# cdf-single-driver.net
KiCad netlist of a schematic drawn in EAGLE
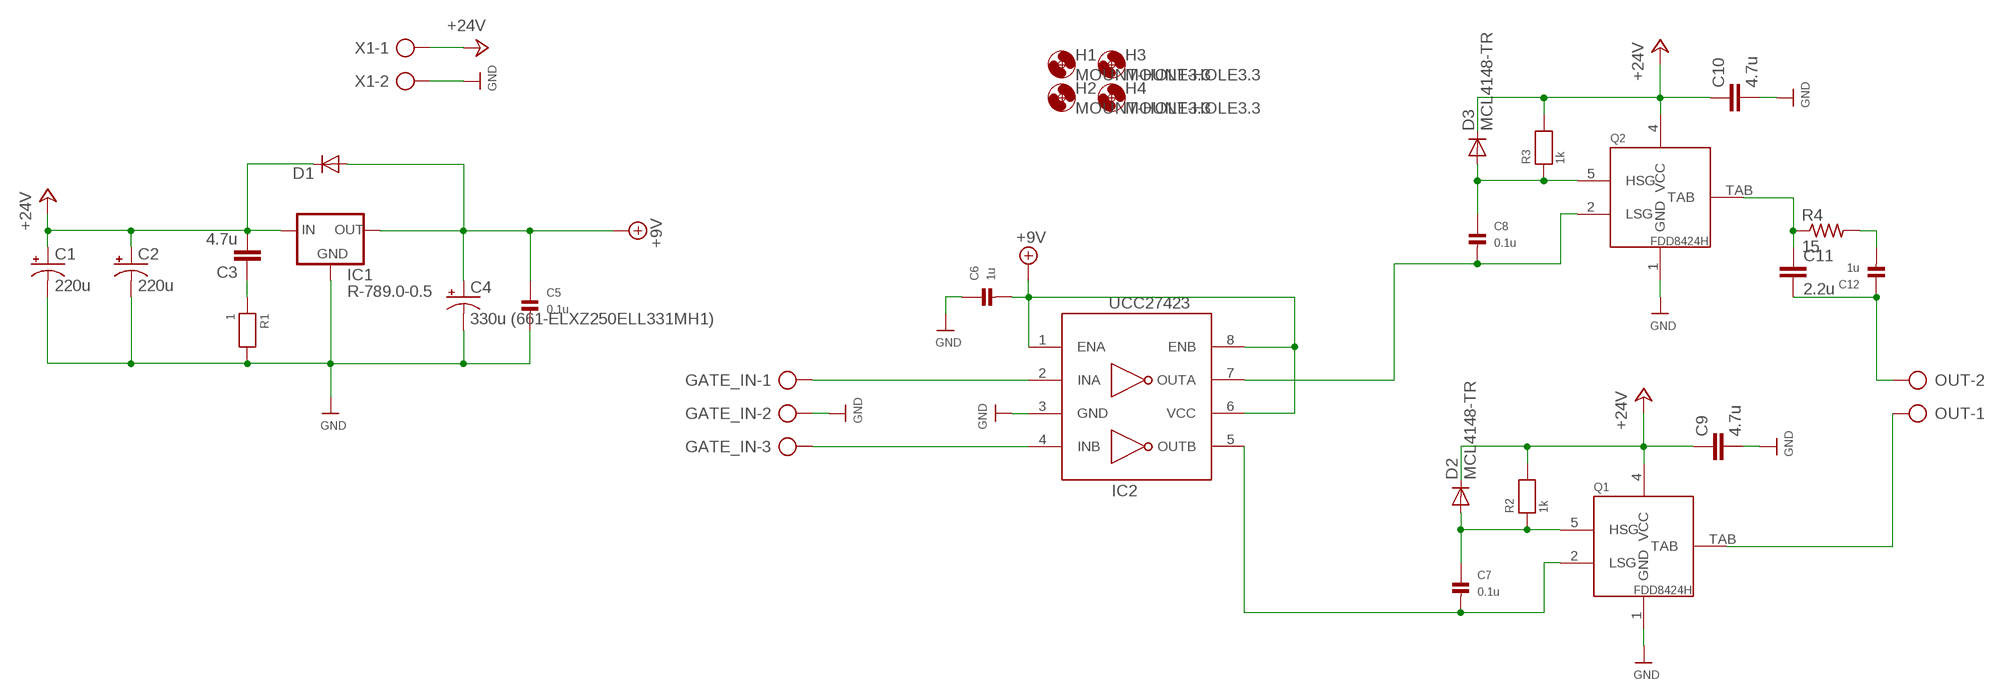
[diagram p0: schematic, sheet 1]

(export (version "E")
  (design (tool "Eeschema 10.0.6"))
  (components
    (comp (ref "C1")
      (value "220u")
      (footprint "eagle-import:E3,5-8")
      (libsource (lib "eagle-import") (part "CPOL-USE3.5-8"))
    )
    (comp (ref "C2")
      (value "220u")
      (footprint "eagle-import:E3,5-8")
      (libsource (lib "eagle-import") (part "CPOL-USE3.5-8"))
    )
    (comp (ref "C3")
      (value "4.7u")
      (footprint "eagle-import:C1210")
      (libsource (lib "eagle-import") (part "C-EUC1210"))
    )
    (comp (ref "C4")
      (value "330u (661-ELXZ250ELL331MH1)")
      (footprint "eagle-import:E3,5-8")
      (libsource (lib "eagle-import") (part "CPOL-USE3.5-8"))
    )
    (comp (ref "C5")
      (value "0.1u")
      (footprint "eagle-import:0805")
      (libsource (lib "eagle-import") (part "CAP_CERAMIC0805"))
    )
    (comp (ref "C6")
      (value "1u")
      (footprint "eagle-import:1206")
      (libsource (lib "eagle-import") (part "CAP_CERAMIC1206"))
    )
    (comp (ref "C7")
      (value "0.1u")
      (footprint "eagle-import:0805")
      (libsource (lib "eagle-import") (part "CAP_CERAMIC0805"))
    )
    (comp (ref "C8")
      (value "0.1u")
      (footprint "eagle-import:0805")
      (libsource (lib "eagle-import") (part "CAP_CERAMIC0805"))
    )
    (comp (ref "C9")
      (value "4.7u")
      (footprint "eagle-import:C1210")
      (libsource (lib "eagle-import") (part "C-EUC1210"))
    )
    (comp (ref "C10")
      (value "4.7u")
      (footprint "eagle-import:C1210")
      (libsource (lib "eagle-import") (part "C-EUC1210"))
    )
    (comp (ref "C11")
      (value "2.2u")
      (footprint "eagle-import:C1210")
      (libsource (lib "eagle-import") (part "C-EUC1210"))
    )
    (comp (ref "C12")
      (value "1u")
      (footprint "eagle-import:1206")
      (libsource (lib "eagle-import") (part "CAP_CERAMIC1206"))
    )
    (comp (ref "D1")
      (value "DIODE-SOD123")
      (footprint "eagle-import:SOD123")
      (libsource (lib "eagle-import") (part "DIODE-SOD123"))
    )
    (comp (ref "D2")
      (value "MCL4148-TR")
      (footprint "eagle-import:MICROMELF-W")
      (libsource (lib "eagle-import") (part "DIODE-MICROMELF-W"))
    )
    (comp (ref "D3")
      (value "MCL4148-TR")
      (footprint "eagle-import:MICROMELF-W")
      (libsource (lib "eagle-import") (part "DIODE-MICROMELF-W"))
    )
    (comp (ref "GATE_IN")
      (value "AK500/3")
      (footprint "eagle-import:AK500_3")
      (libsource (lib "eagle-import") (part "AK500/3"))
    )
    (comp (ref "H1")
      (value "MOUNT-HOLE3.3")
      (footprint "eagle-import:3,3")
      (libsource (lib "eagle-import") (part "MOUNT-HOLE3.3"))
    )
    (comp (ref "H2")
      (value "MOUNT-HOLE3.3")
      (footprint "eagle-import:3,3")
      (libsource (lib "eagle-import") (part "MOUNT-HOLE3.3"))
    )
    (comp (ref "H3")
      (value "MOUNT-HOLE3.3")
      (footprint "eagle-import:3,3")
      (libsource (lib "eagle-import") (part "MOUNT-HOLE3.3"))
    )
    (comp (ref "H4")
      (value "MOUNT-HOLE3.3")
      (footprint "eagle-import:3,3")
      (libsource (lib "eagle-import") (part "MOUNT-HOLE3.3"))
    )
    (comp (ref "IC1")
      (value "R-789.0-0.5")
      (footprint "eagle-import:SIP3")
      (fields (field (name "MF") "Recom") (field (name "MPN") "R-789.0-05"))
      (libsource (lib "eagle-import") (part "R-78-0.59.0"))
    )
    (comp (ref "IC2")
      (value "UCC27423")
      (footprint "eagle-import:SOIC8")
      (libsource (lib "eagle-import") (part "UCC27423"))
    )
    (comp (ref "OUT")
      (value "AK500/2")
      (footprint "eagle-import:AK500_2")
      (libsource (lib "eagle-import") (part "AK500/2"))
    )
    (comp (ref "Q1")
      (value "FDD8424H")
      (footprint "eagle-import:TO252-4")
      (libsource (lib "eagle-import") (part "FDD8424H"))
    )
    (comp (ref "Q2")
      (value "FDD8424H")
      (footprint "eagle-import:TO252-4")
      (libsource (lib "eagle-import") (part "FDD8424H"))
    )
    (comp (ref "R1")
      (value "1")
      (footprint "eagle-import:0805")
      (libsource (lib "eagle-import") (part "RESISTOR0805"))
    )
    (comp (ref "R2")
      (value "1k")
      (footprint "eagle-import:0805")
      (libsource (lib "eagle-import") (part "RESISTOR0805"))
    )
    (comp (ref "R3")
      (value "1k")
      (footprint "eagle-import:0805")
      (libsource (lib "eagle-import") (part "RESISTOR0805"))
    )
    (comp (ref "R4")
      (value "15")
      (footprint "eagle-import:R1210")
      (libsource (lib "eagle-import") (part "R-US_R1210"))
    )
    (comp (ref "X1")
      (value "AK500/2")
      (footprint "eagle-import:AK500_2")
      (libsource (lib "eagle-import") (part "AK500/2"))
    )
  )
  (nets
    (net (code "1") (name "+9V") (class "Default")
      (node (ref "C4") (pin "+") (pinfunction "+_+") (pintype "passive"))
      (node (ref "C5") (pin "1") (pinfunction "P$1_1") (pintype "passive"))
      (node (ref "C6") (pin "2") (pinfunction "P$2_2") (pintype "passive"))
      (node (ref "D1") (pin "A") (pinfunction "A_A") (pintype "passive"))
      (node (ref "IC1") (pin "3") (pinfunction "OUT_3") (pintype "passive"))
      (node (ref "IC2") (pin "1") (pinfunction "ENA_1") (pintype "bidirectional"))
      (node (ref "IC2") (pin "6") (pinfunction "VCC_6") (pintype "bidirectional"))
      (node (ref "IC2") (pin "8") (pinfunction "ENB_8") (pintype "bidirectional"))
    )
    (net (code "2") (name "+24V") (class "Default")
      (node (ref "C1") (pin "+") (pinfunction "+_+") (pintype "passive"))
      (node (ref "C10") (pin "1") (pinfunction "1_1") (pintype "passive"))
      (node (ref "C2") (pin "+") (pinfunction "+_+") (pintype "passive"))
      (node (ref "C3") (pin "2") (pinfunction "2_2") (pintype "passive"))
      (node (ref "C9") (pin "1") (pinfunction "1_1") (pintype "passive"))
      (node (ref "D1") (pin "C") (pinfunction "C_C") (pintype "passive"))
      (node (ref "D2") (pin "C") (pinfunction "C_C") (pintype "passive"))
      (node (ref "D3") (pin "C") (pinfunction "C_C") (pintype "passive"))
      (node (ref "IC1") (pin "1") (pinfunction "IN_1") (pintype "input"))
      (node (ref "Q1") (pin "4") (pinfunction "VCC_4") (pintype "bidirectional"))
      (node (ref "Q2") (pin "4") (pinfunction "VCC_4") (pintype "bidirectional"))
      (node (ref "R2") (pin "2") (pinfunction "2_2") (pintype "passive"))
      (node (ref "R3") (pin "2") (pinfunction "2_2") (pintype "passive"))
      (node (ref "X1") (pin "1") (pinfunction "KL_1") (pintype "passive"))
    )
    (net (code "3") (name "GND") (class "Default")
      (node (ref "C1") (pin "-") (pinfunction "-_-") (pintype "passive"))
      (node (ref "C10") (pin "2") (pinfunction "2_2") (pintype "passive"))
      (node (ref "C2") (pin "-") (pinfunction "-_-") (pintype "passive"))
      (node (ref "C4") (pin "-") (pinfunction "-_-") (pintype "passive"))
      (node (ref "C5") (pin "2") (pinfunction "P$2_2") (pintype "passive"))
      (node (ref "C6") (pin "1") (pinfunction "P$1_1") (pintype "passive"))
      (node (ref "C9") (pin "2") (pinfunction "2_2") (pintype "passive"))
      (node (ref "GATE_IN") (pin "2") (pinfunction "KL_2") (pintype "passive"))
      (node (ref "IC1") (pin "2") (pinfunction "GND_2") (pintype "input"))
      (node (ref "IC2") (pin "3") (pinfunction "GND_3") (pintype "bidirectional"))
      (node (ref "Q1") (pin "1") (pinfunction "GND_1") (pintype "bidirectional"))
      (node (ref "Q2") (pin "1") (pinfunction "GND_1") (pintype "bidirectional"))
      (node (ref "R1") (pin "2") (pinfunction "2_2") (pintype "passive"))
      (node (ref "X1") (pin "2") (pinfunction "KL_2") (pintype "passive"))
    )
    (net (code "4") (name "Net-(C3-Pad1)") (class "Default")
      (node (ref "C3") (pin "1") (pinfunction "1_1") (pintype "passive"))
      (node (ref "R1") (pin "1") (pinfunction "1_1") (pintype "passive"))
    )
    (net (code "5") (name "Net-(C7-P$1)") (class "Default")
      (node (ref "C7") (pin "1") (pinfunction "P$1_1") (pintype "passive"))
      (node (ref "D2") (pin "A") (pinfunction "A_A") (pintype "passive"))
      (node (ref "Q1") (pin "5") (pinfunction "HSG_5") (pintype "bidirectional"))
      (node (ref "R2") (pin "1") (pinfunction "1_1") (pintype "passive"))
    )
    (net (code "6") (name "Net-(C7-P$2)") (class "Default")
      (node (ref "C7") (pin "2") (pinfunction "P$2_2") (pintype "passive"))
      (node (ref "IC2") (pin "5") (pinfunction "OUTB_5") (pintype "bidirectional"))
      (node (ref "Q1") (pin "2") (pinfunction "LSG_2") (pintype "bidirectional"))
    )
    (net (code "7") (name "Net-(C8-P$1)") (class "Default")
      (node (ref "C8") (pin "1") (pinfunction "P$1_1") (pintype "passive"))
      (node (ref "D3") (pin "A") (pinfunction "A_A") (pintype "passive"))
      (node (ref "Q2") (pin "5") (pinfunction "HSG_5") (pintype "bidirectional"))
      (node (ref "R3") (pin "1") (pinfunction "1_1") (pintype "passive"))
    )
    (net (code "8") (name "Net-(C8-P$2)") (class "Default")
      (node (ref "C8") (pin "2") (pinfunction "P$2_2") (pintype "passive"))
      (node (ref "IC2") (pin "7") (pinfunction "OUTA_7") (pintype "bidirectional"))
      (node (ref "Q2") (pin "2") (pinfunction "LSG_2") (pintype "bidirectional"))
    )
    (net (code "9") (name "Net-(C11-Pad1)") (class "Default")
      (node (ref "C11") (pin "1") (pinfunction "1_1") (pintype "passive"))
      (node (ref "Q2") (pin "TAB") (pinfunction "TAB_TAB") (pintype "bidirectional"))
      (node (ref "R4") (pin "1") (pinfunction "1_1") (pintype "passive"))
    )
    (net (code "10") (name "Net-(C12-P$1)") (class "Default")
      (node (ref "C11") (pin "2") (pinfunction "2_2") (pintype "passive"))
      (node (ref "C12") (pin "1") (pinfunction "P$1_1") (pintype "passive"))
      (node (ref "OUT") (pin "2") (pinfunction "KL_2") (pintype "passive"))
    )
    (net (code "11") (name "Net-(C12-P$2)") (class "Default")
      (node (ref "C12") (pin "2") (pinfunction "P$2_2") (pintype "passive"))
      (node (ref "R4") (pin "2") (pinfunction "2_2") (pintype "passive"))
    )
    (net (code "12") (name "Net-(GATE_INA-KL)") (class "Default")
      (node (ref "GATE_IN") (pin "1") (pinfunction "KL_1") (pintype "passive"))
      (node (ref "IC2") (pin "2") (pinfunction "INA_2") (pintype "bidirectional"))
    )
    (net (code "13") (name "Net-(GATE_INC-KL)") (class "Default")
      (node (ref "GATE_IN") (pin "3") (pinfunction "KL_3") (pintype "passive"))
      (node (ref "IC2") (pin "4") (pinfunction "INB_4") (pintype "bidirectional"))
    )
    (net (code "14") (name "Net-(OUTA-KL)") (class "Default")
      (node (ref "OUT") (pin "1") (pinfunction "KL_1") (pintype "passive"))
      (node (ref "Q1") (pin "TAB") (pinfunction "TAB_TAB") (pintype "bidirectional"))
    )
  )
)
